# IR_ID.net
KiCad netlist of a schematic drawn in EAGLE
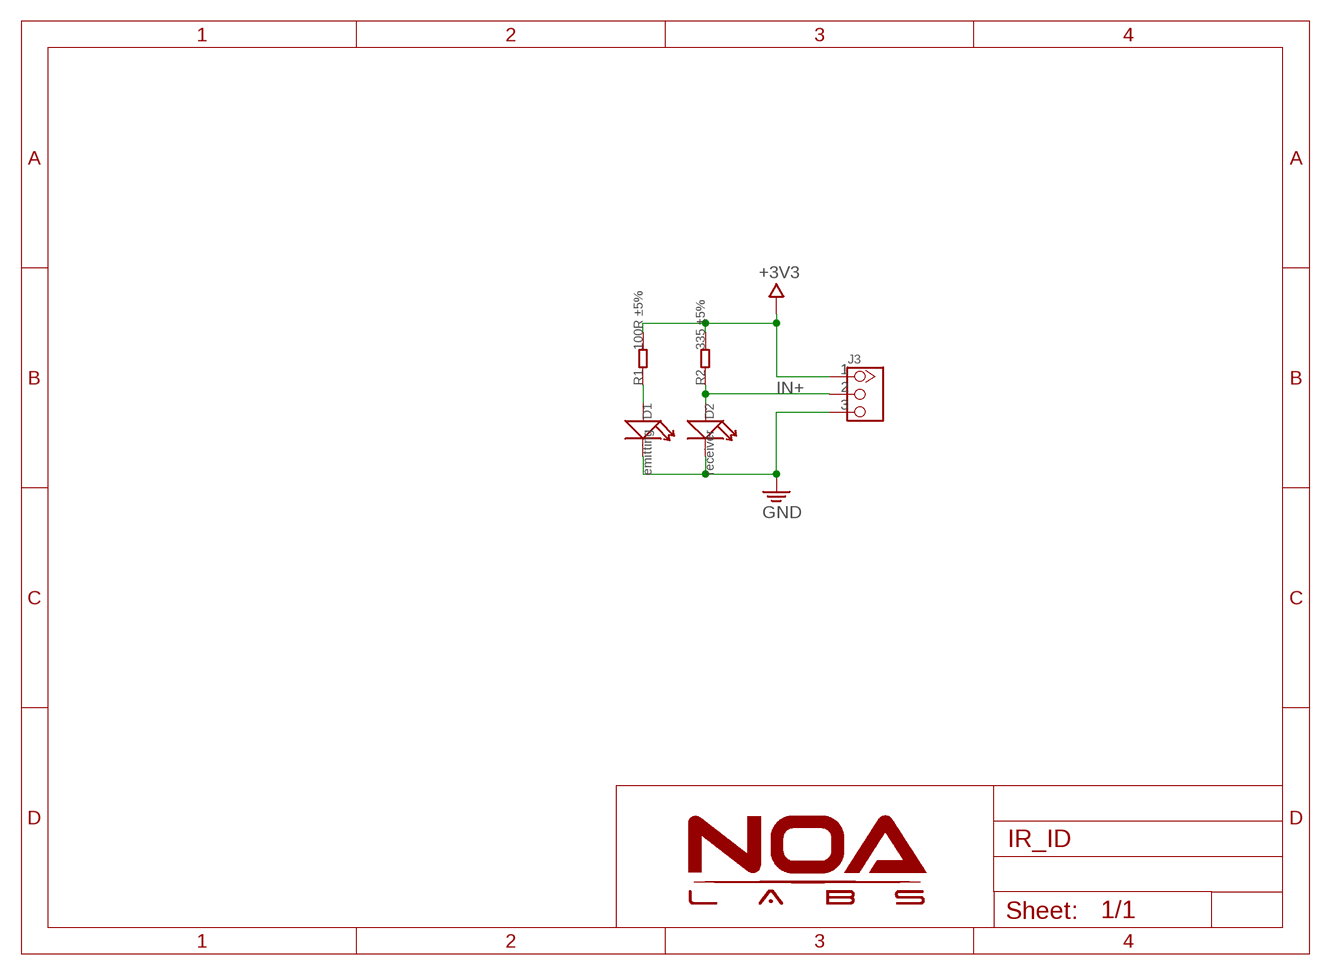
[diagram p0: schematic, sheet 1]

(export (version "E")
  (design (tool "Eeschema 10.0.6"))
  (components
    (comp (ref "D1")
      (value "emitting")
      (footprint "eagle-import:LED-2P-2.54-6MM")
      (libsource (lib "eagle-import") (part "LED-6MM"))
    )
    (comp (ref "D2")
      (value "receiver")
      (footprint "eagle-import:LED-2P-2.54-6MM")
      (libsource (lib "eagle-import") (part "LED-6MM"))
    )
    (comp (ref "J3")
      (value "HEADER-3P-2.54")
      (footprint "eagle-import:3P-2.54")
      (libsource (lib "eagle-import") (part "HEADER-3P-2.54"))
    )
    (comp (ref "R1")
      (value "100R ±5%")
      (footprint "eagle-import:0402")
      (libsource (lib "eagle-import") (part "R-0402"))
    )
    (comp (ref "R2")
      (value "335 ±5%")
      (footprint "eagle-import:0402")
      (libsource (lib "eagle-import") (part "R-0402"))
    )
  )
  (nets
    (net (code "1") (name "+3V3") (class "Default")
      (node (ref "J3") (pin "1") (pinfunction "P$1_1") (pintype "bidirectional"))
      (node (ref "R1") (pin "2") (pinfunction "2_2") (pintype "passive"))
      (node (ref "R2") (pin "2") (pinfunction "2_2") (pintype "passive"))
    )
    (net (code "2") (name "/IN+") (class "Default")
      (node (ref "D2") (pin "+") (pinfunction "+_+") (pintype "passive"))
      (node (ref "J3") (pin "2") (pinfunction "P$2_2") (pintype "bidirectional"))
      (node (ref "R2") (pin "1") (pinfunction "1_1") (pintype "passive"))
    )
    (net (code "3") (name "GND") (class "Default")
      (node (ref "D1") (pin "-") (pinfunction "-_-") (pintype "passive"))
      (node (ref "D2") (pin "-") (pinfunction "-_-") (pintype "passive"))
      (node (ref "J3") (pin "3") (pinfunction "P$3_3") (pintype "bidirectional"))
    )
    (net (code "4") (name "Net-(D1-Pad+)") (class "Default")
      (node (ref "D1") (pin "+") (pinfunction "+_+") (pintype "passive"))
      (node (ref "R1") (pin "1") (pinfunction "1_1") (pintype "passive"))
    )
  )
)
